# p7_1_3v3.net
KiCad netlist of a schematic drawn in EAGLE
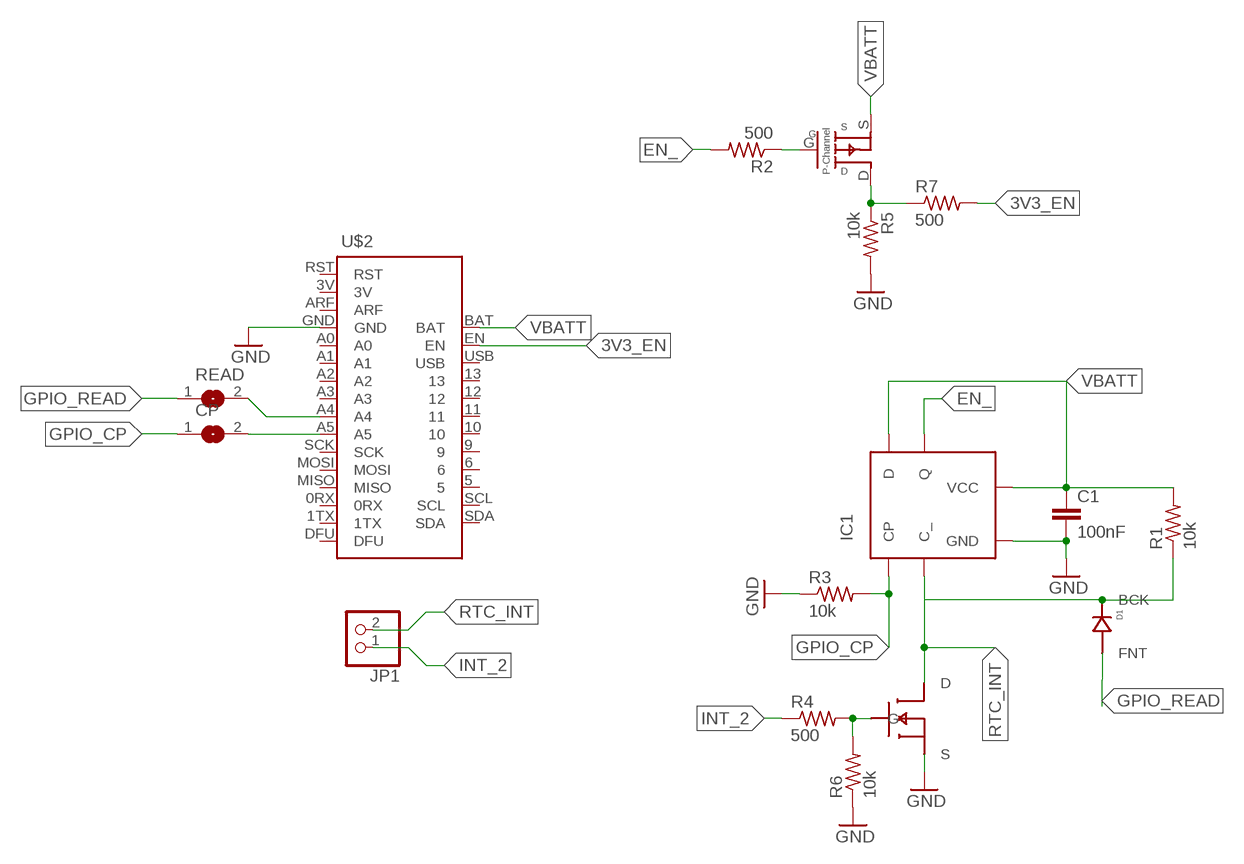
[diagram p0: schematic, sheet 1]

(export (version "E")
  (design (tool "Eeschema 10.0.6"))
  (components
    (comp (ref "C1")
      (value "100nF")
      (footprint "eagle-import:C0805")
      (libsource (lib "eagle-import") (part "C"))
    )
    (comp (ref "CP") (value "SJ") (footprint "eagle-import:SJ") (libsource (lib "eagle-import") (part "SJ")))
    (comp (ref "D1")
      (value "DIODE-DO-214AC")
      (footprint "eagle-import:DIODE-DO-214AC")
      (libsource (lib "eagle-import") (part "DIODE-DO-214AC"))
    )
    (comp (ref "IC1")
      (value "NC7SZ175")
      (footprint "eagle-import:SC70")
      (libsource (lib "eagle-import") (part "NC7SZ175"))
    )
    (comp (ref "JP1")
      (value "PINHD-1X2")
      (footprint "eagle-import:1X02")
      (libsource (lib "eagle-import") (part "PINHD-1X2"))
    )
    (comp (ref "Q1")
      (value "MOSFET-SOT23F")
      (footprint "eagle-import:SOT-23F")
      (libsource (lib "eagle-import") (part "MOSFET-SOT23F"))
    )
    (comp (ref "Q2")
      (value "SSM3J3228R")
      (footprint "eagle-import:SOT-23-3")
      (libsource (lib "eagle-import") (part "SSM3J3228R"))
    )
    (comp (ref "R1")
      (value "10k")
      (footprint "eagle-import:R0805")
      (libsource (lib "eagle-import") (part "R-US_R0805"))
    )
    (comp (ref "R2")
      (value "500")
      (footprint "eagle-import:R0805")
      (libsource (lib "eagle-import") (part "R-US_R0805"))
    )
    (comp (ref "R3")
      (value "10k")
      (footprint "eagle-import:R0805")
      (libsource (lib "eagle-import") (part "R-US_R0805"))
    )
    (comp (ref "R4")
      (value "500")
      (footprint "eagle-import:R0805")
      (libsource (lib "eagle-import") (part "R-US_R0805"))
    )
    (comp (ref "R5")
      (value "10k")
      (footprint "eagle-import:R0805")
      (libsource (lib "eagle-import") (part "R-US_R0805"))
    )
    (comp (ref "R6")
      (value "10k")
      (footprint "eagle-import:R0805")
      (libsource (lib "eagle-import") (part "R-US_R0805"))
    )
    (comp (ref "R7")
      (value "500")
      (footprint "eagle-import:R0805")
      (libsource (lib "eagle-import") (part "R-US_R0805"))
    )
    (comp (ref "READ")
      (value "SJ")
      (footprint "eagle-import:SJ")
      (libsource (lib "eagle-import") (part "SJ"))
    )
    (comp (ref "U$2")
      (value "BLUEFRUIT_M0")
      (footprint "eagle-import:BLUEFRUIT_MO")
      (libsource (lib "eagle-import") (part "BLUEFRUIT_M0"))
    )
  )
  (nets
    (net (code "1") (name "3V3_EN") (class "Default")
      (node (ref "R7") (pin "2") (pinfunction "2_2") (pintype "passive"))
      (node (ref "U$2") (pin "EN") (pinfunction "EN_EN") (pintype "bidirectional"))
    )
    (net (code "2") (name "EN_") (class "Default")
      (node (ref "IC1") (pin "Q") (pinfunction "Q_Q") (pintype "bidirectional"))
      (node (ref "R2") (pin "2") (pinfunction "2_2") (pintype "passive"))
    )
    (net (code "3") (name "GND") (class "Default")
      (node (ref "C1") (pin "2") (pinfunction "2_2") (pintype "passive"))
      (node (ref "IC1") (pin "GND") (pinfunction "GND_GND") (pintype "bidirectional"))
      (node (ref "Q1") (pin "S") (pinfunction "S_S") (pintype "bidirectional"))
      (node (ref "R3") (pin "1") (pinfunction "1_1") (pintype "passive"))
      (node (ref "R5") (pin "2") (pinfunction "2_2") (pintype "passive"))
      (node (ref "R6") (pin "1") (pinfunction "1_1") (pintype "passive"))
      (node (ref "U$2") (pin "GND") (pinfunction "GND_GND") (pintype "bidirectional"))
    )
    (net (code "4") (name "GPIO_CP") (class "Default")
      (node (ref "CP") (pin "1") (pinfunction "1_1") (pintype "passive"))
      (node (ref "IC1") (pin "CP") (pinfunction "CP_CP") (pintype "bidirectional"))
      (node (ref "R3") (pin "2") (pinfunction "2_2") (pintype "passive"))
    )
    (net (code "5") (name "GPIO_READ") (class "Default")
      (node (ref "D1") (pin "FNT") (pinfunction "FNT_FNT") (pintype "bidirectional"))
      (node (ref "READ") (pin "1") (pinfunction "1_1") (pintype "passive"))
    )
    (net (code "6") (name "INT_2") (class "Default")
      (node (ref "JP1") (pin "1") (pinfunction "1_1") (pintype "passive"))
      (node (ref "R4") (pin "1") (pinfunction "1_1") (pintype "passive"))
    )
    (net (code "7") (name "Net-(CP-Pad2)") (class "Default")
      (node (ref "CP") (pin "2") (pinfunction "2_2") (pintype "passive"))
      (node (ref "U$2") (pin "A5") (pinfunction "A5_A5") (pintype "bidirectional"))
    )
    (net (code "8") (name "Net-(Q1-PadG)") (class "Default")
      (node (ref "Q1") (pin "G") (pinfunction "G_G") (pintype "bidirectional"))
      (node (ref "R4") (pin "2") (pinfunction "2_2") (pintype "passive"))
      (node (ref "R6") (pin "2") (pinfunction "2_2") (pintype "passive"))
    )
    (net (code "9") (name "Net-(Q2-PadD)") (class "Default")
      (node (ref "Q2") (pin "D") (pinfunction "D_D") (pintype "bidirectional"))
      (node (ref "R5") (pin "1") (pinfunction "1_1") (pintype "passive"))
      (node (ref "R7") (pin "1") (pinfunction "1_1") (pintype "passive"))
    )
    (net (code "10") (name "Net-(Q2-PadG)") (class "Default")
      (node (ref "Q2") (pin "G") (pinfunction "G_G") (pintype "bidirectional"))
      (node (ref "R2") (pin "1") (pinfunction "1_1") (pintype "passive"))
    )
    (net (code "11") (name "Net-(READ-Pad2)") (class "Default")
      (node (ref "READ") (pin "2") (pinfunction "2_2") (pintype "passive"))
      (node (ref "U$2") (pin "A4") (pinfunction "A4_A4") (pintype "bidirectional"))
    )
    (net (code "12") (name "RTC_INT") (class "Default")
      (node (ref "D1") (pin "BCK") (pinfunction "BCK_BCK") (pintype "bidirectional"))
      (node (ref "IC1") (pin "C_") (pinfunction "C__C_") (pintype "bidirectional"))
      (node (ref "JP1") (pin "2") (pinfunction "2_2") (pintype "passive"))
      (node (ref "Q1") (pin "D") (pinfunction "D_D") (pintype "bidirectional"))
      (node (ref "R1") (pin "1") (pinfunction "1_1") (pintype "passive"))
    )
    (net (code "13") (name "VBATT") (class "Default")
      (node (ref "C1") (pin "1") (pinfunction "1_1") (pintype "passive"))
      (node (ref "IC1") (pin "D") (pinfunction "D_D") (pintype "bidirectional"))
      (node (ref "IC1") (pin "VCC") (pinfunction "VCC_VCC") (pintype "bidirectional"))
      (node (ref "Q2") (pin "S") (pinfunction "S_S") (pintype "bidirectional"))
      (node (ref "R1") (pin "2") (pinfunction "2_2") (pintype "passive"))
      (node (ref "U$2") (pin "BAT") (pinfunction "BAT_BAT") (pintype "bidirectional"))
    )
    (net (code "14") (name "unconnected-(U$2-Pad0RX)") (class "Default")
      (node (ref "U$2") (pin "0RX") (pinfunction "0RX_0RX") (pintype "bidirectional"))
    )
    (net (code "15") (name "unconnected-(U$2-Pad1TX)") (class "Default")
      (node (ref "U$2") (pin "1TX") (pinfunction "1TX_1TX") (pintype "bidirectional"))
    )
    (net (code "16") (name "unconnected-(U$2-Pad3V)") (class "Default")
      (node (ref "U$2") (pin "3V") (pinfunction "3V_3V") (pintype "bidirectional"))
    )
    (net (code "17") (name "unconnected-(U$2-Pad5)") (class "Default")
      (node (ref "U$2") (pin "5") (pinfunction "5_5") (pintype "bidirectional"))
    )
    (net (code "18") (name "unconnected-(U$2-Pad6)") (class "Default")
      (node (ref "U$2") (pin "6") (pinfunction "6_6") (pintype "bidirectional"))
    )
    (net (code "19") (name "unconnected-(U$2-Pad9)") (class "Default")
      (node (ref "U$2") (pin "9") (pinfunction "9_9") (pintype "bidirectional"))
    )
    (net (code "20") (name "unconnected-(U$2-Pad10)") (class "Default")
      (node (ref "U$2") (pin "10") (pinfunction "10_10") (pintype "bidirectional"))
    )
    (net (code "21") (name "unconnected-(U$2-Pad11)") (class "Default")
      (node (ref "U$2") (pin "11") (pinfunction "11_11") (pintype "bidirectional"))
    )
    (net (code "22") (name "unconnected-(U$2-Pad12)") (class "Default")
      (node (ref "U$2") (pin "12") (pinfunction "12_12") (pintype "bidirectional"))
    )
    (net (code "23") (name "unconnected-(U$2-Pad13)") (class "Default")
      (node (ref "U$2") (pin "13") (pinfunction "13_13") (pintype "bidirectional"))
    )
    (net (code "24") (name "unconnected-(U$2-PadA0)") (class "Default")
      (node (ref "U$2") (pin "A0") (pinfunction "A0_A0") (pintype "bidirectional"))
    )
    (net (code "25") (name "unconnected-(U$2-PadA1)") (class "Default")
      (node (ref "U$2") (pin "A1") (pinfunction "A1_A1") (pintype "bidirectional"))
    )
    (net (code "26") (name "unconnected-(U$2-PadA2)") (class "Default")
      (node (ref "U$2") (pin "A2") (pinfunction "A2_A2") (pintype "bidirectional"))
    )
    (net (code "27") (name "unconnected-(U$2-PadA3)") (class "Default")
      (node (ref "U$2") (pin "A3") (pinfunction "A3_A3") (pintype "bidirectional"))
    )
    (net (code "28") (name "unconnected-(U$2-PadARF)") (class "Default")
      (node (ref "U$2") (pin "ARF") (pinfunction "ARF_ARF") (pintype "bidirectional"))
    )
    (net (code "29") (name "unconnected-(U$2-PadDFU)") (class "Default")
      (node (ref "U$2") (pin "DFU") (pinfunction "DFU_DFU") (pintype "bidirectional"))
    )
    (net (code "30") (name "unconnected-(U$2-PadMISO)") (class "Default")
      (node (ref "U$2") (pin "MISO") (pinfunction "MISO_MISO") (pintype "bidirectional"))
    )
    (net (code "31") (name "unconnected-(U$2-PadMOSI)") (class "Default")
      (node (ref "U$2") (pin "MOSI") (pinfunction "MOSI_MOSI") (pintype "bidirectional"))
    )
    (net (code "32") (name "unconnected-(U$2-PadRST)") (class "Default")
      (node (ref "U$2") (pin "RST") (pinfunction "RST_RST") (pintype "bidirectional"))
    )
    (net (code "33") (name "unconnected-(U$2-PadSCK)") (class "Default")
      (node (ref "U$2") (pin "SCK") (pinfunction "SCK_SCK") (pintype "bidirectional"))
    )
    (net (code "34") (name "unconnected-(U$2-PadSCL)") (class "Default")
      (node (ref "U$2") (pin "SCL") (pinfunction "SCL_SCL") (pintype "bidirectional"))
    )
    (net (code "35") (name "unconnected-(U$2-PadSDA)") (class "Default")
      (node (ref "U$2") (pin "SDA") (pinfunction "SDA_SDA") (pintype "bidirectional"))
    )
    (net (code "36") (name "unconnected-(U$2-PadUSB)") (class "Default")
      (node (ref "U$2") (pin "USB") (pinfunction "USB_USB") (pintype "bidirectional"))
    )
  )
)
